# ms1616.net
KiCad netlist of a schematic drawn in EAGLE
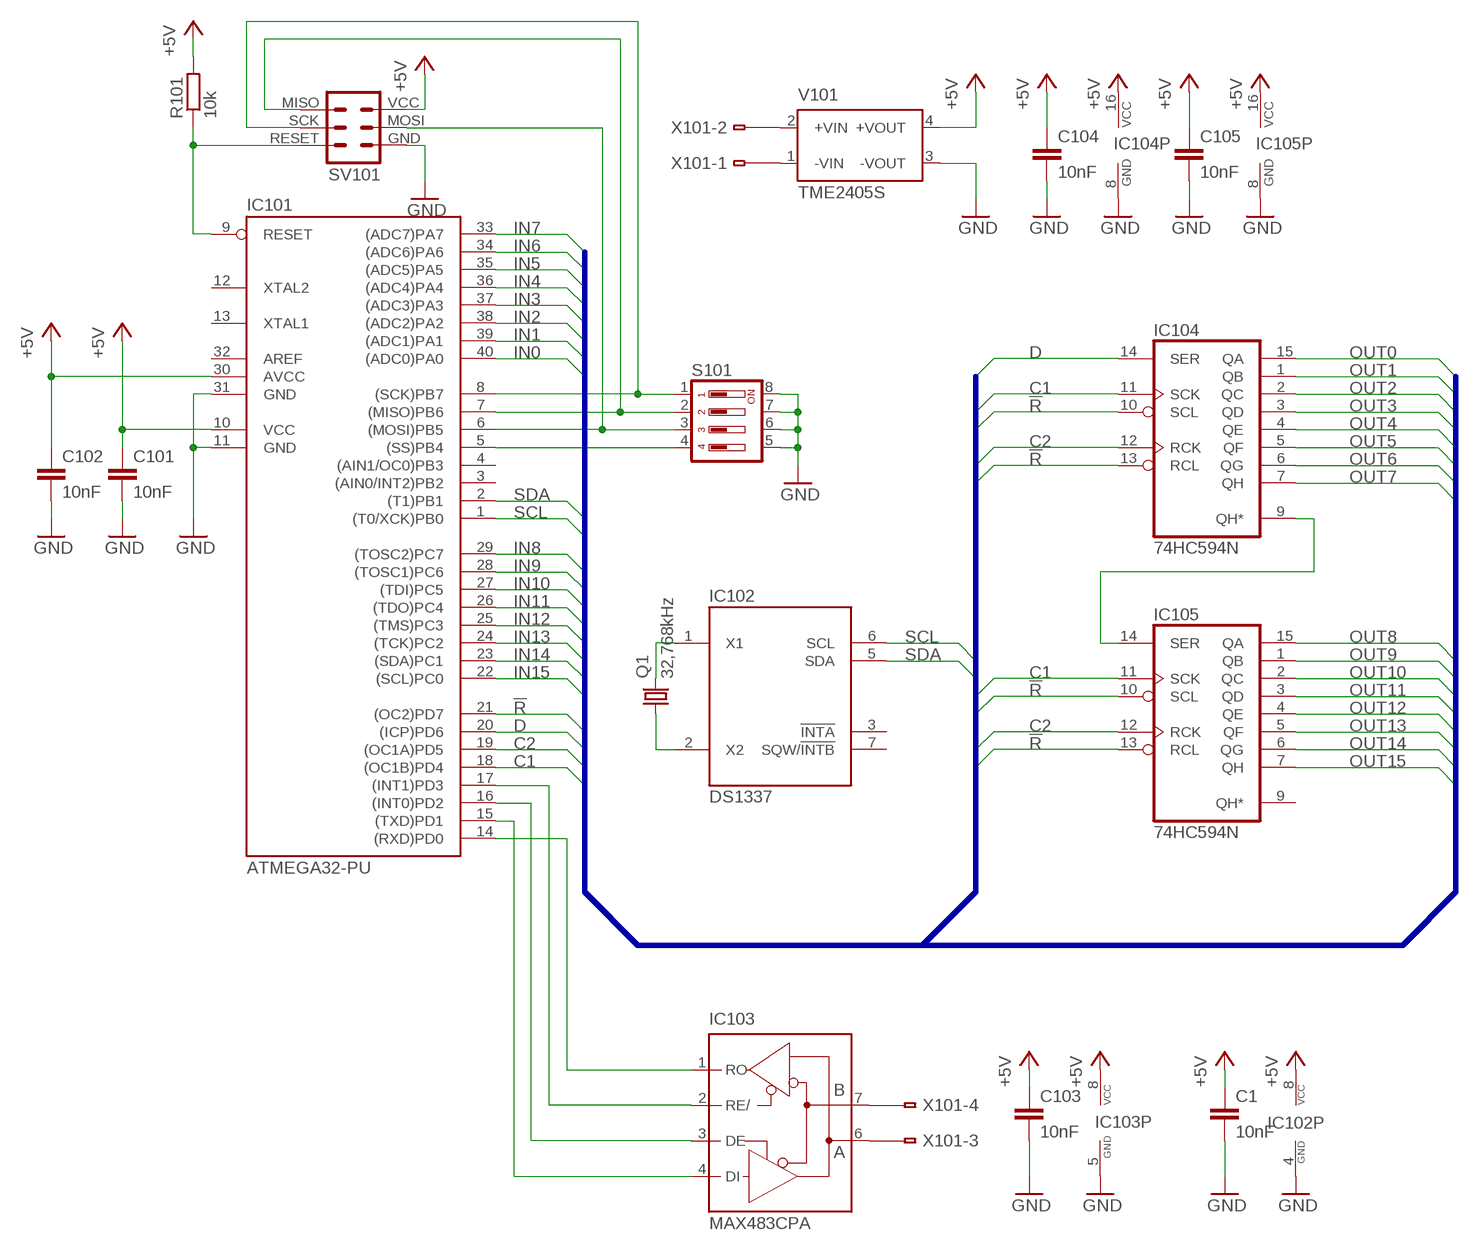
[diagram p0: schematic, sheet 1]
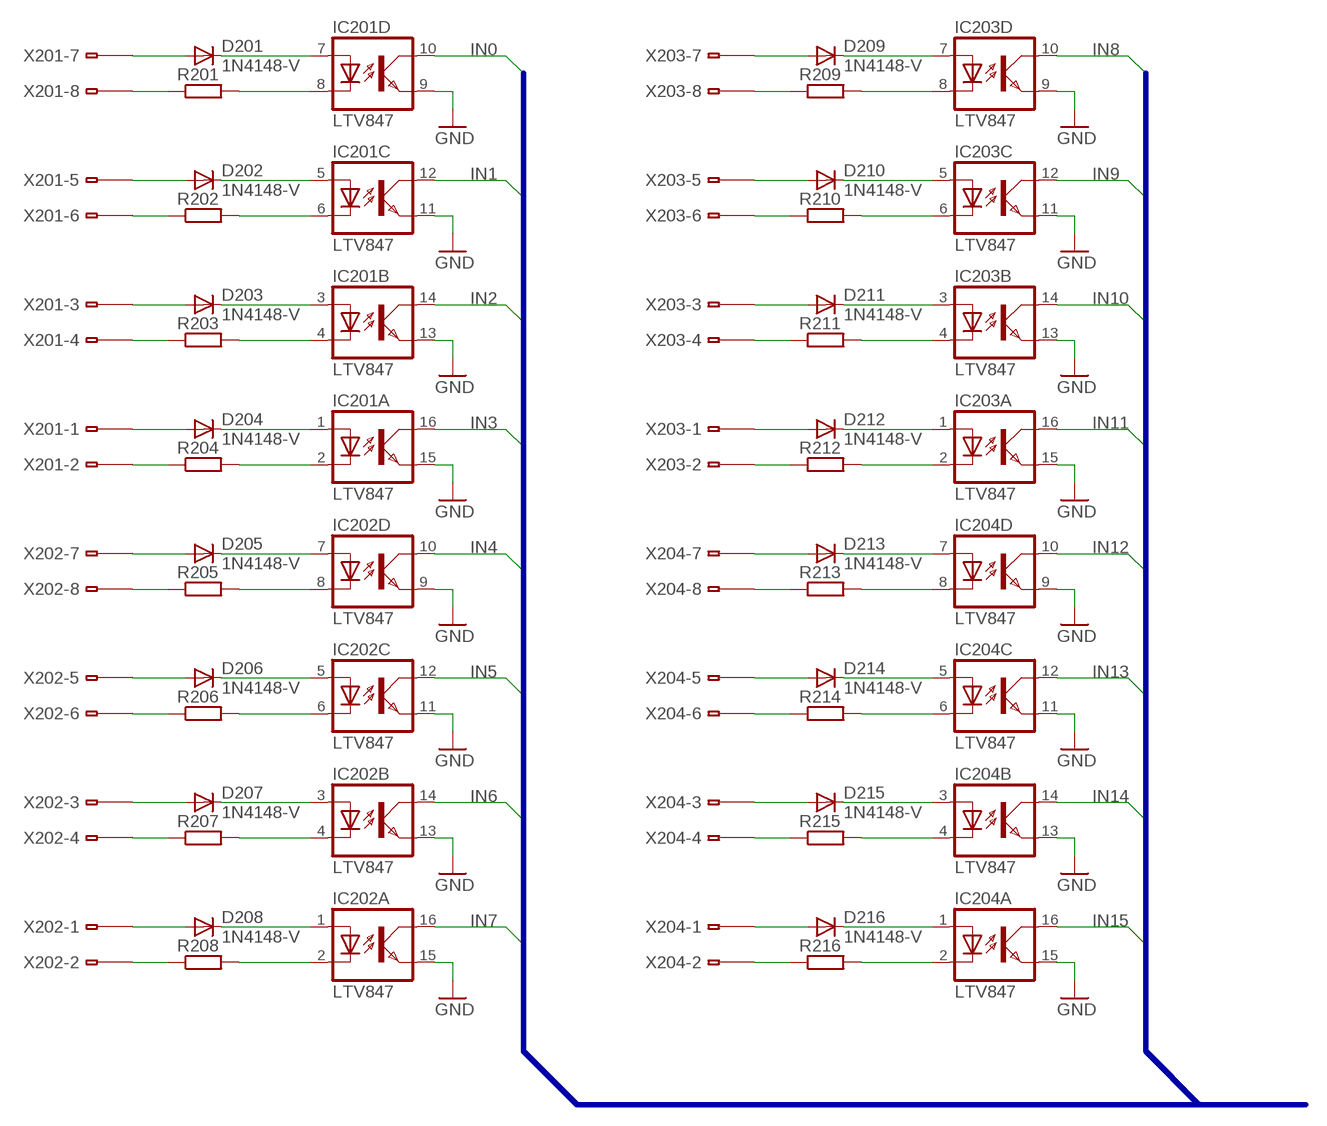
[diagram p1: schematic, sheet 2]
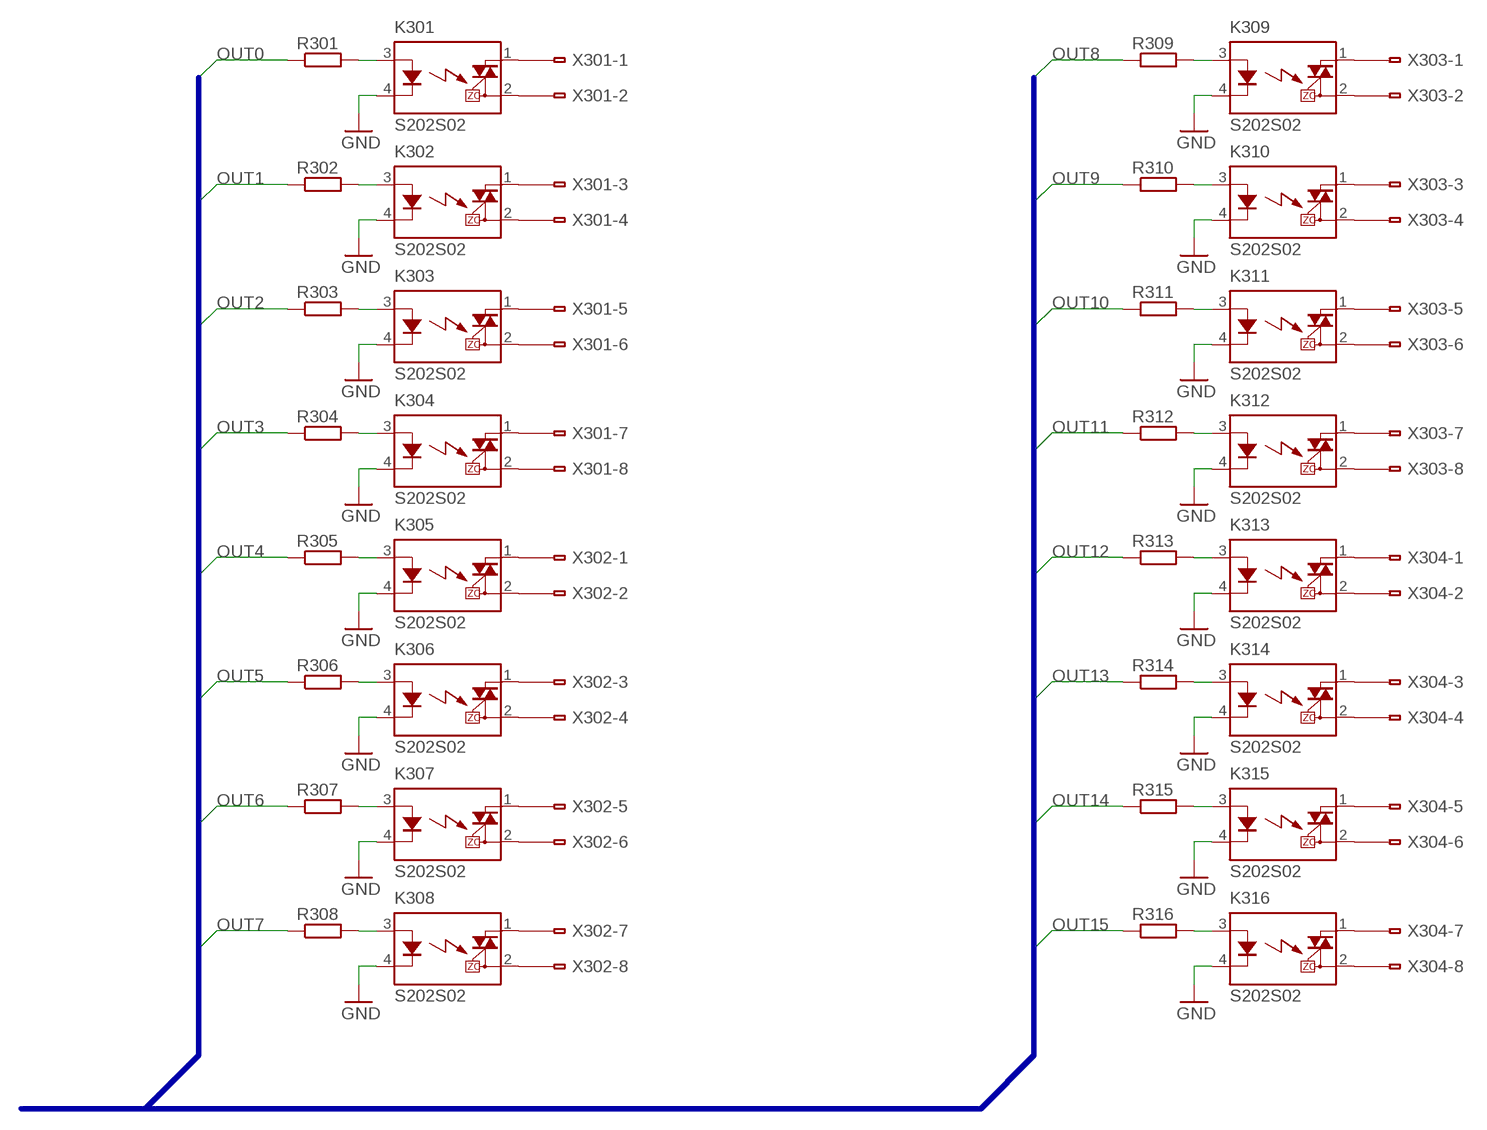
[diagram p2: schematic, sheet 3]

(export (version "E")
  (design (tool "Eeschema 10.0.6"))
  (components
    (comp (ref "K301")
      (value "S202S02")
      (footprint "eagle-import:SIP4")
      (libsource (lib "eagle-import") (part "S02S022"))
    )
    (comp (ref "K302")
      (value "S202S02")
      (footprint "eagle-import:SIP4")
      (libsource (lib "eagle-import") (part "S02S022"))
    )
    (comp (ref "K303")
      (value "S202S02")
      (footprint "eagle-import:SIP4")
      (libsource (lib "eagle-import") (part "S02S022"))
    )
    (comp (ref "K304")
      (value "S202S02")
      (footprint "eagle-import:SIP4")
      (libsource (lib "eagle-import") (part "S02S022"))
    )
    (comp (ref "K305")
      (value "S202S02")
      (footprint "eagle-import:SIP4")
      (libsource (lib "eagle-import") (part "S02S022"))
    )
    (comp (ref "K306")
      (value "S202S02")
      (footprint "eagle-import:SIP4")
      (libsource (lib "eagle-import") (part "S02S022"))
    )
    (comp (ref "K307")
      (value "S202S02")
      (footprint "eagle-import:SIP4")
      (libsource (lib "eagle-import") (part "S02S022"))
    )
    (comp (ref "K308")
      (value "S202S02")
      (footprint "eagle-import:SIP4")
      (libsource (lib "eagle-import") (part "S02S022"))
    )
    (comp (ref "K309")
      (value "S202S02")
      (footprint "eagle-import:SIP4")
      (libsource (lib "eagle-import") (part "S02S022"))
    )
    (comp (ref "K310")
      (value "S202S02")
      (footprint "eagle-import:SIP4")
      (libsource (lib "eagle-import") (part "S02S022"))
    )
    (comp (ref "K311")
      (value "S202S02")
      (footprint "eagle-import:SIP4")
      (libsource (lib "eagle-import") (part "S02S022"))
    )
    (comp (ref "K312")
      (value "S202S02")
      (footprint "eagle-import:SIP4")
      (libsource (lib "eagle-import") (part "S02S022"))
    )
    (comp (ref "K313")
      (value "S202S02")
      (footprint "eagle-import:SIP4")
      (libsource (lib "eagle-import") (part "S02S022"))
    )
    (comp (ref "K314")
      (value "S202S02")
      (footprint "eagle-import:SIP4")
      (libsource (lib "eagle-import") (part "S02S022"))
    )
    (comp (ref "K315")
      (value "S202S02")
      (footprint "eagle-import:SIP4")
      (libsource (lib "eagle-import") (part "S02S022"))
    )
    (comp (ref "K316")
      (value "S202S02")
      (footprint "eagle-import:SIP4")
      (libsource (lib "eagle-import") (part "S02S022"))
    )
    (comp (ref "R301")
      (value "R_0204/2V")
      (footprint "eagle-import:0204V")
      (libsource (lib "eagle-import") (part "R_0204/2V"))
    )
    (comp (ref "R302")
      (value "R_0204/2V")
      (footprint "eagle-import:0204V")
      (libsource (lib "eagle-import") (part "R_0204/2V"))
    )
    (comp (ref "R303")
      (value "R_0204/2V")
      (footprint "eagle-import:0204V")
      (libsource (lib "eagle-import") (part "R_0204/2V"))
    )
    (comp (ref "R304")
      (value "R_0204/2V")
      (footprint "eagle-import:0204V")
      (libsource (lib "eagle-import") (part "R_0204/2V"))
    )
    (comp (ref "R305")
      (value "R_0204/2V")
      (footprint "eagle-import:0204V")
      (libsource (lib "eagle-import") (part "R_0204/2V"))
    )
    (comp (ref "R306")
      (value "R_0204/2V")
      (footprint "eagle-import:0204V")
      (libsource (lib "eagle-import") (part "R_0204/2V"))
    )
    (comp (ref "R307")
      (value "R_0204/2V")
      (footprint "eagle-import:0204V")
      (libsource (lib "eagle-import") (part "R_0204/2V"))
    )
    (comp (ref "R308")
      (value "R_0204/2V")
      (footprint "eagle-import:0204V")
      (libsource (lib "eagle-import") (part "R_0204/2V"))
    )
    (comp (ref "R309")
      (value "R_0204/2V")
      (footprint "eagle-import:0204V")
      (libsource (lib "eagle-import") (part "R_0204/2V"))
    )
    (comp (ref "R310")
      (value "R_0204/2V")
      (footprint "eagle-import:0204V")
      (libsource (lib "eagle-import") (part "R_0204/2V"))
    )
    (comp (ref "R311")
      (value "R_0204/2V")
      (footprint "eagle-import:0204V")
      (libsource (lib "eagle-import") (part "R_0204/2V"))
    )
    (comp (ref "R312")
      (value "R_0204/2V")
      (footprint "eagle-import:0204V")
      (libsource (lib "eagle-import") (part "R_0204/2V"))
    )
    (comp (ref "R313")
      (value "R_0204/2V")
      (footprint "eagle-import:0204V")
      (libsource (lib "eagle-import") (part "R_0204/2V"))
    )
    (comp (ref "R314")
      (value "R_0204/2V")
      (footprint "eagle-import:0204V")
      (libsource (lib "eagle-import") (part "R_0204/2V"))
    )
    (comp (ref "R315")
      (value "R_0204/2V")
      (footprint "eagle-import:0204V")
      (libsource (lib "eagle-import") (part "R_0204/2V"))
    )
    (comp (ref "R316")
      (value "R_0204/2V")
      (footprint "eagle-import:0204V")
      (libsource (lib "eagle-import") (part "R_0204/2V"))
    )
    (comp (ref "X301")
      (value "233-508")
      (footprint "eagle-import:233-508")
      (libsource (lib "eagle-import") (part "233-508"))
    )
    (comp (ref "X302")
      (value "233-508")
      (footprint "eagle-import:233-508")
      (libsource (lib "eagle-import") (part "233-508"))
    )
    (comp (ref "X303")
      (value "233-508")
      (footprint "eagle-import:233-508")
      (libsource (lib "eagle-import") (part "233-508"))
    )
    (comp (ref "X304")
      (value "233-508")
      (footprint "eagle-import:233-508")
      (libsource (lib "eagle-import") (part "233-508"))
    )
    (comp (ref "C1")
      (value "10nF")
      (footprint "eagle-import:C025-025X050")
      (libsource (lib "eagle-import") (part "C_025-025X050"))
    )
    (comp (ref "C101")
      (value "10nF")
      (footprint "eagle-import:C025-025X050")
      (libsource (lib "eagle-import") (part "C_025-025X050"))
    )
    (comp (ref "C102")
      (value "10nF")
      (footprint "eagle-import:C025-025X050")
      (libsource (lib "eagle-import") (part "C_025-025X050"))
    )
    (comp (ref "C103")
      (value "10nF")
      (footprint "eagle-import:C025-025X050")
      (libsource (lib "eagle-import") (part "C_025-025X050"))
    )
    (comp (ref "C104")
      (value "10nF")
      (footprint "eagle-import:C025-025X050")
      (libsource (lib "eagle-import") (part "C_025-025X050"))
    )
    (comp (ref "C105")
      (value "10nF")
      (footprint "eagle-import:C025-025X050")
      (libsource (lib "eagle-import") (part "C_025-025X050"))
    )
    (comp (ref "IC101")
      (value "ATMEGA32-PU")
      (footprint "eagle-import:DIL40")
      (libsource (lib "eagle-import") (part "ATMEGA32-PU"))
    )
    (comp (ref "IC102")
      (value "DS1337")
      (footprint "eagle-import:DIL08")
      (libsource (lib "eagle-import") (part "DS1337"))
    )
    (comp (ref "IC103")
      (value "MAX483CPA")
      (footprint "eagle-import:DIL08")
      (libsource (lib "eagle-import") (part "MAX48CPA3"))
    )
    (comp (ref "IC104")
      (value "74HC594N")
      (footprint "eagle-import:DIL16")
      (libsource (lib "eagle-import") (part "74594NHC"))
    )
    (comp (ref "IC105")
      (value "74HC594N")
      (footprint "eagle-import:DIL16")
      (libsource (lib "eagle-import") (part "74594NHC"))
    )
    (comp (ref "Q1")
      (value "32,768kHz")
      (footprint "eagle-import:HC49_S")
      (libsource (lib "eagle-import") (part "Q_HC49S"))
    )
    (comp (ref "R101")
      (value "10k")
      (footprint "eagle-import:0204V")
      (libsource (lib "eagle-import") (part "R_0204/2V"))
    )
    (comp (ref "S101")
      (value "DIP04YL")
      (footprint "eagle-import:DIP04YL")
      (libsource (lib "eagle-import") (part "DIP04YL"))
    )
    (comp (ref "SV101")
      (value "AVR_ISP6")
      (footprint "eagle-import:ML6")
      (libsource (lib "eagle-import") (part "AVR_ISP6"))
    )
    (comp (ref "V101")
      (value "TME2405S")
      (footprint "eagle-import:TME-24V")
      (fields
        (field (name "MPN") "TME 2405S")
        (field (name "MPN_1") "TME 2405S")
        (field (name "OC_FARNELL") "1007547")
        (field (name "OC_NEWARK") "51R5329")
      )
      (libsource (lib "eagle-import") (part "TME?2405S"))
    )
    (comp (ref "X101")
      (value "233-504")
      (footprint "eagle-import:233-504")
      (libsource (lib "eagle-import") (part "233-504"))
    )
    (comp (ref "D201")
      (value "1N4148-V")
      (footprint "eagle-import:DO35-V")
      (libsource (lib "eagle-import") (part "1N4148-V"))
    )
    (comp (ref "D202")
      (value "1N4148-V")
      (footprint "eagle-import:DO35-V")
      (libsource (lib "eagle-import") (part "1N4148-V"))
    )
    (comp (ref "D203")
      (value "1N4148-V")
      (footprint "eagle-import:DO35-V")
      (libsource (lib "eagle-import") (part "1N4148-V"))
    )
    (comp (ref "D204")
      (value "1N4148-V")
      (footprint "eagle-import:DO35-V")
      (libsource (lib "eagle-import") (part "1N4148-V"))
    )
    (comp (ref "D205")
      (value "1N4148-V")
      (footprint "eagle-import:DO35-V")
      (libsource (lib "eagle-import") (part "1N4148-V"))
    )
    (comp (ref "D206")
      (value "1N4148-V")
      (footprint "eagle-import:DO35-V")
      (libsource (lib "eagle-import") (part "1N4148-V"))
    )
    (comp (ref "D207")
      (value "1N4148-V")
      (footprint "eagle-import:DO35-V")
      (libsource (lib "eagle-import") (part "1N4148-V"))
    )
    (comp (ref "D208")
      (value "1N4148-V")
      (footprint "eagle-import:DO35-V")
      (libsource (lib "eagle-import") (part "1N4148-V"))
    )
    (comp (ref "D209")
      (value "1N4148-V")
      (footprint "eagle-import:DO35-V")
      (libsource (lib "eagle-import") (part "1N4148-V"))
    )
    (comp (ref "D210")
      (value "1N4148-V")
      (footprint "eagle-import:DO35-V")
      (libsource (lib "eagle-import") (part "1N4148-V"))
    )
    (comp (ref "D211")
      (value "1N4148-V")
      (footprint "eagle-import:DO35-V")
      (libsource (lib "eagle-import") (part "1N4148-V"))
    )
    (comp (ref "D212")
      (value "1N4148-V")
      (footprint "eagle-import:DO35-V")
      (libsource (lib "eagle-import") (part "1N4148-V"))
    )
    (comp (ref "D213")
      (value "1N4148-V")
      (footprint "eagle-import:DO35-V")
      (libsource (lib "eagle-import") (part "1N4148-V"))
    )
    (comp (ref "D214")
      (value "1N4148-V")
      (footprint "eagle-import:DO35-V")
      (libsource (lib "eagle-import") (part "1N4148-V"))
    )
    (comp (ref "D215")
      (value "1N4148-V")
      (footprint "eagle-import:DO35-V")
      (libsource (lib "eagle-import") (part "1N4148-V"))
    )
    (comp (ref "D216")
      (value "1N4148-V")
      (footprint "eagle-import:DO35-V")
      (libsource (lib "eagle-import") (part "1N4148-V"))
    )
    (comp (ref "IC201")
      (value "LTV847")
      (footprint "eagle-import:DIL16")
      (libsource (lib "eagle-import") (part "LTV847"))
    )
    (comp (ref "IC202")
      (value "LTV847")
      (footprint "eagle-import:DIL16")
      (libsource (lib "eagle-import") (part "LTV847"))
    )
    (comp (ref "IC203")
      (value "LTV847")
      (footprint "eagle-import:DIL16")
      (libsource (lib "eagle-import") (part "LTV847"))
    )
    (comp (ref "IC204")
      (value "LTV847")
      (footprint "eagle-import:DIL16")
      (libsource (lib "eagle-import") (part "LTV847"))
    )
    (comp (ref "R201")
      (value "R_0204/2V")
      (footprint "eagle-import:0204V")
      (libsource (lib "eagle-import") (part "R_0204/2V"))
    )
    (comp (ref "R202")
      (value "R_0204/2V")
      (footprint "eagle-import:0204V")
      (libsource (lib "eagle-import") (part "R_0204/2V"))
    )
    (comp (ref "R203")
      (value "R_0204/2V")
      (footprint "eagle-import:0204V")
      (libsource (lib "eagle-import") (part "R_0204/2V"))
    )
    (comp (ref "R204")
      (value "R_0204/2V")
      (footprint "eagle-import:0204V")
      (libsource (lib "eagle-import") (part "R_0204/2V"))
    )
    (comp (ref "R205")
      (value "R_0204/2V")
      (footprint "eagle-import:0204V")
      (libsource (lib "eagle-import") (part "R_0204/2V"))
    )
    (comp (ref "R206")
      (value "R_0204/2V")
      (footprint "eagle-import:0204V")
      (libsource (lib "eagle-import") (part "R_0204/2V"))
    )
    (comp (ref "R207")
      (value "R_0204/2V")
      (footprint "eagle-import:0204V")
      (libsource (lib "eagle-import") (part "R_0204/2V"))
    )
    (comp (ref "R208")
      (value "R_0204/2V")
      (footprint "eagle-import:0204V")
      (libsource (lib "eagle-import") (part "R_0204/2V"))
    )
    (comp (ref "R209")
      (value "R_0204/2V")
      (footprint "eagle-import:0204V")
      (libsource (lib "eagle-import") (part "R_0204/2V"))
    )
    (comp (ref "R210")
      (value "R_0204/2V")
      (footprint "eagle-import:0204V")
      (libsource (lib "eagle-import") (part "R_0204/2V"))
    )
    (comp (ref "R211")
      (value "R_0204/2V")
      (footprint "eagle-import:0204V")
      (libsource (lib "eagle-import") (part "R_0204/2V"))
    )
    (comp (ref "R212")
      (value "R_0204/2V")
      (footprint "eagle-import:0204V")
      (libsource (lib "eagle-import") (part "R_0204/2V"))
    )
    (comp (ref "R213")
      (value "R_0204/2V")
      (footprint "eagle-import:0204V")
      (libsource (lib "eagle-import") (part "R_0204/2V"))
    )
    (comp (ref "R214")
      (value "R_0204/2V")
      (footprint "eagle-import:0204V")
      (libsource (lib "eagle-import") (part "R_0204/2V"))
    )
    (comp (ref "R215")
      (value "R_0204/2V")
      (footprint "eagle-import:0204V")
      (libsource (lib "eagle-import") (part "R_0204/2V"))
    )
    (comp (ref "R216")
      (value "R_0204/2V")
      (footprint "eagle-import:0204V")
      (libsource (lib "eagle-import") (part "R_0204/2V"))
    )
    (comp (ref "X201")
      (value "233-508")
      (footprint "eagle-import:233-508")
      (libsource (lib "eagle-import") (part "233-508"))
    )
    (comp (ref "X202")
      (value "233-508")
      (footprint "eagle-import:233-508")
      (libsource (lib "eagle-import") (part "233-508"))
    )
    (comp (ref "X203")
      (value "233-508")
      (footprint "eagle-import:233-508")
      (libsource (lib "eagle-import") (part "233-508"))
    )
    (comp (ref "X204")
      (value "233-508")
      (footprint "eagle-import:233-508")
      (libsource (lib "eagle-import") (part "233-508"))
    )
  )
  (nets
    (net (code "1") (name "+5V") (class "Default")
      (node (ref "C1") (pin "1") (pinfunction "1_1") (pintype "passive"))
      (node (ref "C101") (pin "1") (pinfunction "1_1") (pintype "passive"))
      (node (ref "C102") (pin "1") (pinfunction "1_1") (pintype "passive"))
      (node (ref "C103") (pin "1") (pinfunction "1_1") (pintype "passive"))
      (node (ref "C104") (pin "1") (pinfunction "1_1") (pintype "passive"))
      (node (ref "C105") (pin "1") (pinfunction "1_1") (pintype "passive"))
      (node (ref "IC101") (pin "10") (pinfunction "VCC_10") (pintype "power_in"))
      (node (ref "IC101") (pin "30") (pinfunction "AVCC_30") (pintype "power_in"))
      (node (ref "IC102") (pin "8") (pinfunction "VCC_8") (pintype "power_in"))
      (node (ref "IC103") (pin "8") (pinfunction "VCC_8") (pintype "power_in"))
      (node (ref "IC104") (pin "16") (pinfunction "VCC_16") (pintype "power_in"))
      (node (ref "IC105") (pin "16") (pinfunction "VCC_16") (pintype "power_in"))
      (node (ref "R101") (pin "2") (pinfunction "2_2") (pintype "passive"))
      (node (ref "SV101") (pin "VCC") (pinfunction "VCC_VCC") (pintype "passive"))
      (node (ref "V101") (pin "4") (pinfunction "+VOUT_4") (pintype "passive"))
    )
    (net (code "2") (name "C1") (class "Default")
      (node (ref "IC101") (pin "18") (pinfunction "(OC1B)PD4_18") (pintype "bidirectional"))
      (node (ref "IC104") (pin "11") (pinfunction "SCK_11") (pintype "input"))
      (node (ref "IC105") (pin "11") (pinfunction "SCK_11") (pintype "input"))
    )
    (net (code "3") (name "C2") (class "Default")
      (node (ref "IC101") (pin "19") (pinfunction "(OC1A)PD5_19") (pintype "bidirectional"))
      (node (ref "IC104") (pin "12") (pinfunction "RCK_12") (pintype "input"))
      (node (ref "IC105") (pin "12") (pinfunction "RCK_12") (pintype "input"))
    )
    (net (code "4") (name "D") (class "Default")
      (node (ref "IC101") (pin "20") (pinfunction "(ICP)PD6_20") (pintype "bidirectional"))
      (node (ref "IC104") (pin "14") (pinfunction "SER_14") (pintype "input"))
    )
    (net (code "5") (name "GND") (class "Default")
      (node (ref "C1") (pin "2") (pinfunction "2_2") (pintype "passive"))
      (node (ref "C101") (pin "2") (pinfunction "2_2") (pintype "passive"))
      (node (ref "C102") (pin "2") (pinfunction "2_2") (pintype "passive"))
      (node (ref "C103") (pin "2") (pinfunction "2_2") (pintype "passive"))
      (node (ref "C104") (pin "2") (pinfunction "2_2") (pintype "passive"))
      (node (ref "C105") (pin "2") (pinfunction "2_2") (pintype "passive"))
      (node (ref "IC101") (pin "11") (pinfunction "GND_11") (pintype "power_in"))
      (node (ref "IC101") (pin "31") (pinfunction "GND_31") (pintype "power_in"))
      (node (ref "IC102") (pin "4") (pinfunction "GND_4") (pintype "power_in"))
      (node (ref "IC103") (pin "5") (pinfunction "GND_5") (pintype "power_in"))
      (node (ref "IC104") (pin "8") (pinfunction "GND_8") (pintype "power_in"))
      (node (ref "IC105") (pin "8") (pinfunction "GND_8") (pintype "power_in"))
      (node (ref "IC201") (pin "11") (pinfunction "EMIT_11") (pintype "passive"))
      (node (ref "IC201") (pin "13") (pinfunction "EMIT_13") (pintype "passive"))
      (node (ref "IC201") (pin "15") (pinfunction "EMIT_15") (pintype "passive"))
      (node (ref "IC201") (pin "9") (pinfunction "EMIT_9") (pintype "passive"))
      (node (ref "IC202") (pin "11") (pinfunction "EMIT_11") (pintype "passive"))
      (node (ref "IC202") (pin "13") (pinfunction "EMIT_13") (pintype "passive"))
      (node (ref "IC202") (pin "15") (pinfunction "EMIT_15") (pintype "passive"))
      (node (ref "IC202") (pin "9") (pinfunction "EMIT_9") (pintype "passive"))
      (node (ref "IC203") (pin "11") (pinfunction "EMIT_11") (pintype "passive"))
      (node (ref "IC203") (pin "13") (pinfunction "EMIT_13") (pintype "passive"))
      (node (ref "IC203") (pin "15") (pinfunction "EMIT_15") (pintype "passive"))
      (node (ref "IC203") (pin "9") (pinfunction "EMIT_9") (pintype "passive"))
      (node (ref "IC204") (pin "11") (pinfunction "EMIT_11") (pintype "passive"))
      (node (ref "IC204") (pin "13") (pinfunction "EMIT_13") (pintype "passive"))
      (node (ref "IC204") (pin "15") (pinfunction "EMIT_15") (pintype "passive"))
      (node (ref "IC204") (pin "9") (pinfunction "EMIT_9") (pintype "passive"))
      (node (ref "K301") (pin "4") (pinfunction "K_4") (pintype "passive"))
      (node (ref "K302") (pin "4") (pinfunction "K_4") (pintype "passive"))
      (node (ref "K303") (pin "4") (pinfunction "K_4") (pintype "passive"))
      (node (ref "K304") (pin "4") (pinfunction "K_4") (pintype "passive"))
      (node (ref "K305") (pin "4") (pinfunction "K_4") (pintype "passive"))
      (node (ref "K306") (pin "4") (pinfunction "K_4") (pintype "passive"))
      (node (ref "K307") (pin "4") (pinfunction "K_4") (pintype "passive"))
      (node (ref "K308") (pin "4") (pinfunction "K_4") (pintype "passive"))
      (node (ref "K309") (pin "4") (pinfunction "K_4") (pintype "passive"))
      (node (ref "K310") (pin "4") (pinfunction "K_4") (pintype "passive"))
      (node (ref "K311") (pin "4") (pinfunction "K_4") (pintype "passive"))
      (node (ref "K312") (pin "4") (pinfunction "K_4") (pintype "passive"))
      (node (ref "K313") (pin "4") (pinfunction "K_4") (pintype "passive"))
      (node (ref "K314") (pin "4") (pinfunction "K_4") (pintype "passive"))
      (node (ref "K315") (pin "4") (pinfunction "K_4") (pintype "passive"))
      (node (ref "K316") (pin "4") (pinfunction "K_4") (pintype "passive"))
      (node (ref "S101") (pin "5") (pinfunction "5_5") (pintype "passive"))
      (node (ref "S101") (pin "6") (pinfunction "6_6") (pintype "passive"))
      (node (ref "S101") (pin "7") (pinfunction "7_7") (pintype "passive"))
      (node (ref "S101") (pin "8") (pinfunction "8_8") (pintype "passive"))
      (node (ref "SV101") (pin "GND") (pinfunction "GND_GND") (pintype "passive"))
      (node (ref "V101") (pin "3") (pinfunction "-VOUT_3") (pintype "passive"))
    )
    (net (code "6") (name "IN0") (class "Default")
      (node (ref "IC101") (pin "40") (pinfunction "(ADC0)PA0_40") (pintype "bidirectional"))
      (node (ref "IC201") (pin "10") (pinfunction "COL_10") (pintype "passive"))
    )
    (net (code "7") (name "IN1") (class "Default")
      (node (ref "IC101") (pin "39") (pinfunction "(ADC1)PA1_39") (pintype "bidirectional"))
      (node (ref "IC201") (pin "12") (pinfunction "COL_12") (pintype "passive"))
    )
    (net (code "8") (name "IN2") (class "Default")
      (node (ref "IC101") (pin "38") (pinfunction "(ADC2)PA2_38") (pintype "bidirectional"))
      (node (ref "IC201") (pin "14") (pinfunction "COL_14") (pintype "passive"))
    )
    (net (code "9") (name "IN3") (class "Default")
      (node (ref "IC101") (pin "37") (pinfunction "(ADC3)PA3_37") (pintype "bidirectional"))
      (node (ref "IC201") (pin "16") (pinfunction "COL_16") (pintype "passive"))
    )
    (net (code "10") (name "IN4") (class "Default")
      (node (ref "IC101") (pin "36") (pinfunction "(ADC4)PA4_36") (pintype "bidirectional"))
      (node (ref "IC202") (pin "10") (pinfunction "COL_10") (pintype "passive"))
    )
    (net (code "11") (name "IN5") (class "Default")
      (node (ref "IC101") (pin "35") (pinfunction "(ADC5)PA5_35") (pintype "bidirectional"))
      (node (ref "IC202") (pin "12") (pinfunction "COL_12") (pintype "passive"))
    )
    (net (code "12") (name "IN6") (class "Default")
      (node (ref "IC101") (pin "34") (pinfunction "(ADC6)PA6_34") (pintype "bidirectional"))
      (node (ref "IC202") (pin "14") (pinfunction "COL_14") (pintype "passive"))
    )
    (net (code "13") (name "IN7") (class "Default")
      (node (ref "IC101") (pin "33") (pinfunction "(ADC7)PA7_33") (pintype "bidirectional"))
      (node (ref "IC202") (pin "16") (pinfunction "COL_16") (pintype "passive"))
    )
    (net (code "14") (name "IN8") (class "Default")
      (node (ref "IC101") (pin "29") (pinfunction "(TOSC2)PC7_29") (pintype "bidirectional"))
      (node (ref "IC203") (pin "10") (pinfunction "COL_10") (pintype "passive"))
    )
    (net (code "15") (name "IN9") (class "Default")
      (node (ref "IC101") (pin "28") (pinfunction "(TOSC1)PC6_28") (pintype "bidirectional"))
      (node (ref "IC203") (pin "12") (pinfunction "COL_12") (pintype "passive"))
    )
    (net (code "16") (name "IN10") (class "Default")
      (node (ref "IC101") (pin "27") (pinfunction "(TDI)PC5_27") (pintype "bidirectional"))
      (node (ref "IC203") (pin "14") (pinfunction "COL_14") (pintype "passive"))
    )
    (net (code "17") (name "IN11") (class "Default")
      (node (ref "IC101") (pin "26") (pinfunction "(TDO)PC4_26") (pintype "bidirectional"))
      (node (ref "IC203") (pin "16") (pinfunction "COL_16") (pintype "passive"))
    )
    (net (code "18") (name "IN12") (class "Default")
      (node (ref "IC101") (pin "25") (pinfunction "(TMS)PC3_25") (pintype "bidirectional"))
      (node (ref "IC204") (pin "10") (pinfunction "COL_10") (pintype "passive"))
    )
    (net (code "19") (name "IN13") (class "Default")
      (node (ref "IC101") (pin "24") (pinfunction "(TCK)PC2_24") (pintype "bidirectional"))
      (node (ref "IC204") (pin "12") (pinfunction "COL_12") (pintype "passive"))
    )
    (net (code "20") (name "IN14") (class "Default")
      (node (ref "IC101") (pin "23") (pinfunction "(SDA)PC1_23") (pintype "bidirectional"))
      (node (ref "IC204") (pin "14") (pinfunction "COL_14") (pintype "passive"))
    )
    (net (code "21") (name "IN15") (class "Default")
      (node (ref "IC101") (pin "22") (pinfunction "(SCL)PC0_22") (pintype "bidirectional"))
      (node (ref "IC204") (pin "16") (pinfunction "COL_16") (pintype "passive"))
    )
    (net (code "22") (name "Net-(D201-A)") (class "Default")
      (node (ref "D201") (pin "1") (pinfunction "A_1") (pintype "passive"))
      (node (ref "X201") (pin "A7") (pinfunction "-1_A7") (pintype "passive"))
    )
    (net (code "23") (name "Net-(D201-C)") (class "Default")
      (node (ref "D201") (pin "2") (pinfunction "C_2") (pintype "passive"))
      (node (ref "IC201") (pin "7") (pinfunction "A_7") (pintype "passive"))
    )
    (net (code "24") (name "Net-(D202-A)") (class "Default")
      (node (ref "D202") (pin "1") (pinfunction "A_1") (pintype "passive"))
      (node (ref "X201") (pin "A5") (pinfunction "-1_A5") (pintype "passive"))
    )
    (net (code "25") (name "Net-(D202-C)") (class "Default")
      (node (ref "D202") (pin "2") (pinfunction "C_2") (pintype "passive"))
      (node (ref "IC201") (pin "5") (pinfunction "A_5") (pintype "passive"))
    )
    (net (code "26") (name "Net-(D203-A)") (class "Default")
      (node (ref "D203") (pin "1") (pinfunction "A_1") (pintype "passive"))
      (node (ref "X201") (pin "A3") (pinfunction "-1_A3") (pintype "passive"))
    )
    (net (code "27") (name "Net-(D203-C)") (class "Default")
      (node (ref "D203") (pin "2") (pinfunction "C_2") (pintype "passive"))
      (node (ref "IC201") (pin "3") (pinfunction "A_3") (pintype "passive"))
    )
    (net (code "28") (name "Net-(D204-A)") (class "Default")
      (node (ref "D204") (pin "1") (pinfunction "A_1") (pintype "passive"))
      (node (ref "X201") (pin "A1") (pinfunction "-1_A1") (pintype "passive"))
    )
    (net (code "29") (name "Net-(D204-C)") (class "Default")
      (node (ref "D204") (pin "2") (pinfunction "C_2") (pintype "passive"))
      (node (ref "IC201") (pin "1") (pinfunction "A_1") (pintype "passive"))
    )
    (net (code "30") (name "Net-(D205-A)") (class "Default")
      (node (ref "D205") (pin "1") (pinfunction "A_1") (pintype "passive"))
      (node (ref "X202") (pin "A7") (pinfunction "-1_A7") (pintype "passive"))
    )
    (net (code "31") (name "Net-(D205-C)") (class "Default")
      (node (ref "D205") (pin "2") (pinfunction "C_2") (pintype "passive"))
      (node (ref "IC202") (pin "7") (pinfunction "A_7") (pintype "passive"))
    )
    (net (code "32") (name "Net-(D206-A)") (class "Default")
      (node (ref "D206") (pin "1") (pinfunction "A_1") (pintype "passive"))
      (node (ref "X202") (pin "A5") (pinfunction "-1_A5") (pintype "passive"))
    )
    (net (code "33") (name "Net-(D206-C)") (class "Default")
      (node (ref "D206") (pin "2") (pinfunction "C_2") (pintype "passive"))
      (node (ref "IC202") (pin "5") (pinfunction "A_5") (pintype "passive"))
    )
    (net (code "34") (name "Net-(D207-A)") (class "Default")
      (node (ref "D207") (pin "1") (pinfunction "A_1") (pintype "passive"))
      (node (ref "X202") (pin "A3") (pinfunction "-1_A3") (pintype "passive"))
    )
    (net (code "35") (name "Net-(D207-C)") (class "Default")
      (node (ref "D207") (pin "2") (pinfunction "C_2") (pintype "passive"))
      (node (ref "IC202") (pin "3") (pinfunction "A_3") (pintype "passive"))
    )
    (net (code "36") (name "Net-(D208-A)") (class "Default")
      (node (ref "D208") (pin "1") (pinfunction "A_1") (pintype "passive"))
      (node (ref "X202") (pin "A1") (pinfunction "-1_A1") (pintype "passive"))
    )
    (net (code "37") (name "Net-(D208-C)") (class "Default")
      (node (ref "D208") (pin "2") (pinfunction "C_2") (pintype "passive"))
      (node (ref "IC202") (pin "1") (pinfunction "A_1") (pintype "passive"))
    )
    (net (code "38") (name "Net-(D209-A)") (class "Default")
      (node (ref "D209") (pin "1") (pinfunction "A_1") (pintype "passive"))
      (node (ref "X203") (pin "A7") (pinfunction "-1_A7") (pintype "passive"))
    )
    (net (code "39") (name "Net-(D209-C)") (class "Default")
      (node (ref "D209") (pin "2") (pinfunction "C_2") (pintype "passive"))
      (node (ref "IC203") (pin "7") (pinfunction "A_7") (pintype "passive"))
    )
    (net (code "40") (name "Net-(D210-A)") (class "Default")
      (node (ref "D210") (pin "1") (pinfunction "A_1") (pintype "passive"))
      (node (ref "X203") (pin "A5") (pinfunction "-1_A5") (pintype "passive"))
    )
    (net (code "41") (name "Net-(D210-C)") (class "Default")
      (node (ref "D210") (pin "2") (pinfunction "C_2") (pintype "passive"))
      (node (ref "IC203") (pin "5") (pinfunction "A_5") (pintype "passive"))
    )
    (net (code "42") (name "Net-(D211-A)") (class "Default")
      (node (ref "D211") (pin "1") (pinfunction "A_1") (pintype "passive"))
      (node (ref "X203") (pin "A3") (pinfunction "-1_A3") (pintype "passive"))
    )
    (net (code "43") (name "Net-(D211-C)") (class "Default")
      (node (ref "D211") (pin "2") (pinfunction "C_2") (pintype "passive"))
      (node (ref "IC203") (pin "3") (pinfunction "A_3") (pintype "passive"))
    )
    (net (code "44") (name "Net-(D212-A)") (class "Default")
      (node (ref "D212") (pin "1") (pinfunction "A_1") (pintype "passive"))
      (node (ref "X203") (pin "A1") (pinfunction "-1_A1") (pintype "passive"))
    )
    (net (code "45") (name "Net-(D212-C)") (class "Default")
      (node (ref "D212") (pin "2") (pinfunction "C_2") (pintype "passive"))
      (node (ref "IC203") (pin "1") (pinfunction "A_1") (pintype "passive"))
    )
    (net (code "46") (name "Net-(D213-A)") (class "Default")
      (node (ref "D213") (pin "1") (pinfunction "A_1") (pintype "passive"))
      (node (ref "X204") (pin "A7") (pinfunction "-1_A7") (pintype "passive"))
    )
    (net (code "47") (name "Net-(D213-C)") (class "Default")
      (node (ref "D213") (pin "2") (pinfunction "C_2") (pintype "passive"))
      (node (ref "IC204") (pin "7") (pinfunction "A_7") (pintype "passive"))
    )
    (net (code "48") (name "Net-(D214-A)") (class "Default")
      (node (ref "D214") (pin "1") (pinfunction "A_1") (pintype "passive"))
      (node (ref "X204") (pin "A5") (pinfunction "-1_A5") (pintype "passive"))
    )
    (net (code "49") (name "Net-(D214-C)") (class "Default")
      (node (ref "D214") (pin "2") (pinfunction "C_2") (pintype "passive"))
      (node (ref "IC204") (pin "5") (pinfunction "A_5") (pintype "passive"))
    )
    (net (code "50") (name "Net-(D215-A)") (class "Default")
      (node (ref "D215") (pin "1") (pinfunction "A_1") (pintype "passive"))
      (node (ref "X204") (pin "A3") (pinfunction "-1_A3") (pintype "passive"))
    )
    (net (code "51") (name "Net-(D215-C)") (class "Default")
      (node (ref "D215") (pin "2") (pinfunction "C_2") (pintype "passive"))
      (node (ref "IC204") (pin "3") (pinfunction "A_3") (pintype "passive"))
    )
    (net (code "52") (name "Net-(D216-A)") (class "Default")
      (node (ref "D216") (pin "1") (pinfunction "A_1") (pintype "passive"))
      (node (ref "X204") (pin "A1") (pinfunction "-1_A1") (pintype "passive"))
    )
    (net (code "53") (name "Net-(D216-C)") (class "Default")
      (node (ref "D216") (pin "2") (pinfunction "C_2") (pintype "passive"))
      (node (ref "IC204") (pin "1") (pinfunction "A_1") (pintype "passive"))
    )
    (net (code "54") (name "Net-(IC101-(INT0)PD2)") (class "Default")
      (node (ref "IC101") (pin "16") (pinfunction "(INT0)PD2_16") (pintype "bidirectional"))
      (node (ref "IC103") (pin "3") (pinfunction "DE_3") (pintype "input"))
    )
    (net (code "55") (name "Net-(IC101-(INT1)PD3)") (class "Default")
      (node (ref "IC101") (pin "17") (pinfunction "(INT1)PD3_17") (pintype "bidirectional"))
      (node (ref "IC103") (pin "2") (pinfunction "RE/_2") (pintype "input"))
    )
    (net (code "56") (name "Net-(IC101-(MISO)PB6)") (class "Default")
      (node (ref "IC101") (pin "7") (pinfunction "(MISO)PB6_7") (pintype "bidirectional"))
      (node (ref "S101") (pin "2") (pinfunction "2_2") (pintype "passive"))
      (node (ref "SV101") (pin "MISO") (pinfunction "MISO_MISO") (pintype "passive"))
    )
    (net (code "57") (name "Net-(IC101-(MOSI)PB5)") (class "Default")
      (node (ref "IC101") (pin "6") (pinfunction "(MOSI)PB5_6") (pintype "bidirectional"))
      (node (ref "S101") (pin "3") (pinfunction "3_3") (pintype "passive"))
      (node (ref "SV101") (pin "MOSI") (pinfunction "MOSI_MOSI") (pintype "passive"))
    )
    (net (code "58") (name "Net-(IC101-(RXD)PD0)") (class "Default")
      (node (ref "IC101") (pin "14") (pinfunction "(RXD)PD0_14") (pintype "bidirectional"))
      (node (ref "IC103") (pin "1") (pinfunction "RO_1") (pintype "output"))
    )
    (net (code "59") (name "Net-(IC101-(SCK)PB7)") (class "Default")
      (node (ref "IC101") (pin "8") (pinfunction "(SCK)PB7_8") (pintype "bidirectional"))
      (node (ref "S101") (pin "1") (pinfunction "1_1") (pintype "passive"))
      (node (ref "SV101") (pin "SCK") (pinfunction "SCK_SCK") (pintype "passive"))
    )
    (net (code "60") (name "Net-(IC101-(SS)PB4)") (class "Default")
      (node (ref "IC101") (pin "5") (pinfunction "(SS)PB4_5") (pintype "bidirectional"))
      (node (ref "S101") (pin "4") (pinfunction "4_4") (pintype "passive"))
    )
    (net (code "61") (name "Net-(IC101-(TXD)PD1)") (class "Default")
      (node (ref "IC101") (pin "15") (pinfunction "(TXD)PD1_15") (pintype "bidirectional"))
      (node (ref "IC103") (pin "4") (pinfunction "DI_4") (pintype "input"))
    )
    (net (code "62") (name "Net-(IC101-RESET)") (class "Default")
      (node (ref "IC101") (pin "9") (pinfunction "RESET_9") (pintype "input"))
      (node (ref "R101") (pin "1") (pinfunction "1_1") (pintype "passive"))
      (node (ref "SV101") (pin "RESET") (pinfunction "RESET_RESET") (pintype "passive"))
    )
    (net (code "63") (name "Net-(IC102A-X1)") (class "Default")
      (node (ref "IC102") (pin "1") (pinfunction "X1_1") (pintype "bidirectional"))
      (node (ref "Q1") (pin "2") (pinfunction "2_2") (pintype "passive"))
    )
    (net (code "64") (name "Net-(IC102A-X2)") (class "Default")
      (node (ref "IC102") (pin "2") (pinfunction "X2_2") (pintype "bidirectional"))
      (node (ref "Q1") (pin "1") (pinfunction "1_1") (pintype "passive"))
    )
    (net (code "65") (name "Net-(IC103A-A)") (class "Default")
      (node (ref "IC103") (pin "6") (pinfunction "A_6") (pintype "passive"))
      (node (ref "X101") (pin "A3") (pinfunction "-1_A3") (pintype "passive"))
    )
    (net (code "66") (name "Net-(IC103A-B)") (class "Default")
      (node (ref "IC103") (pin "7") (pinfunction "B_7") (pintype "passive"))
      (node (ref "X101") (pin "A4") (pinfunction "-1_A4") (pintype "passive"))
    )
    (net (code "67") (name "Net-(IC104A-QH*)") (class "Default")
      (node (ref "IC104") (pin "9") (pinfunction "QH*_9") (pintype "output"))
      (node (ref "IC105") (pin "14") (pinfunction "SER_14") (pintype "input"))
    )
    (net (code "68") (name "Net-(IC201A-C)") (class "Default")
      (node (ref "IC201") (pin "2") (pinfunction "C_2") (pintype "passive"))
      (node (ref "R204") (pin "2") (pinfunction "2_2") (pintype "passive"))
    )
    (net (code "69") (name "Net-(IC201B-C)") (class "Default")
      (node (ref "IC201") (pin "4") (pinfunction "C_4") (pintype "passive"))
      (node (ref "R203") (pin "2") (pinfunction "2_2") (pintype "passive"))
    )
    (net (code "70") (name "Net-(IC201C-C)") (class "Default")
      (node (ref "IC201") (pin "6") (pinfunction "C_6") (pintype "passive"))
      (node (ref "R202") (pin "2") (pinfunction "2_2") (pintype "passive"))
    )
    (net (code "71") (name "Net-(IC201D-C)") (class "Default")
      (node (ref "IC201") (pin "8") (pinfunction "C_8") (pintype "passive"))
      (node (ref "R201") (pin "2") (pinfunction "2_2") (pintype "passive"))
    )
    (net (code "72") (name "Net-(IC202A-C)") (class "Default")
      (node (ref "IC202") (pin "2") (pinfunction "C_2") (pintype "passive"))
      (node (ref "R208") (pin "2") (pinfunction "2_2") (pintype "passive"))
    )
    (net (code "73") (name "Net-(IC202B-C)") (class "Default")
      (node (ref "IC202") (pin "4") (pinfunction "C_4") (pintype "passive"))
      (node (ref "R207") (pin "2") (pinfunction "2_2") (pintype "passive"))
    )
    (net (code "74") (name "Net-(IC202C-C)") (class "Default")
      (node (ref "IC202") (pin "6") (pinfunction "C_6") (pintype "passive"))
      (node (ref "R206") (pin "2") (pinfunction "2_2") (pintype "passive"))
    )
    (net (code "75") (name "Net-(IC202D-C)") (class "Default")
      (node (ref "IC202") (pin "8") (pinfunction "C_8") (pintype "passive"))
      (node (ref "R205") (pin "2") (pinfunction "2_2") (pintype "passive"))
    )
    (net (code "76") (name "Net-(IC203A-C)") (class "Default")
      (node (ref "IC203") (pin "2") (pinfunction "C_2") (pintype "passive"))
      (node (ref "R212") (pin "2") (pinfunction "2_2") (pintype "passive"))
    )
    (net (code "77") (name "Net-(IC203B-C)") (class "Default")
      (node (ref "IC203") (pin "4") (pinfunction "C_4") (pintype "passive"))
      (node (ref "R211") (pin "2") (pinfunction "2_2") (pintype "passive"))
    )
    (net (code "78") (name "Net-(IC203C-C)") (class "Default")
      (node (ref "IC203") (pin "6") (pinfunction "C_6") (pintype "passive"))
      (node (ref "R210") (pin "2") (pinfunction "2_2") (pintype "passive"))
    )
    (net (code "79") (name "Net-(IC203D-C)") (class "Default")
      (node (ref "IC203") (pin "8") (pinfunction "C_8") (pintype "passive"))
      (node (ref "R209") (pin "2") (pinfunction "2_2") (pintype "passive"))
    )
    (net (code "80") (name "Net-(IC204A-C)") (class "Default")
      (node (ref "IC204") (pin "2") (pinfunction "C_2") (pintype "passive"))
      (node (ref "R216") (pin "2") (pinfunction "2_2") (pintype "passive"))
    )
    (net (code "81") (name "Net-(IC204B-C)") (class "Default")
      (node (ref "IC204") (pin "4") (pinfunction "C_4") (pintype "passive"))
      (node (ref "R215") (pin "2") (pinfunction "2_2") (pintype "passive"))
    )
    (net (code "82") (name "Net-(IC204C-C)") (class "Default")
      (node (ref "IC204") (pin "6") (pinfunction "C_6") (pintype "passive"))
      (node (ref "R214") (pin "2") (pinfunction "2_2") (pintype "passive"))
    )
    (net (code "83") (name "Net-(IC204D-C)") (class "Default")
      (node (ref "IC204") (pin "8") (pinfunction "C_8") (pintype "passive"))
      (node (ref "R213") (pin "2") (pinfunction "2_2") (pintype "passive"))
    )
    (net (code "84") (name "Net-(K301-A)") (class "Default")
      (node (ref "K301") (pin "3") (pinfunction "A_3") (pintype "passive"))
      (node (ref "R301") (pin "2") (pinfunction "2_2") (pintype "passive"))
    )
    (net (code "85") (name "Net-(K301-DS1)") (class "Default")
      (node (ref "K301") (pin "1") (pinfunction "DS1_1") (pintype "passive"))
      (node (ref "X301") (pin "A1") (pinfunction "-1_A1") (pintype "passive"))
    )
    (net (code "86") (name "Net-(K301-DS2)") (class "Default")
      (node (ref "K301") (pin "2") (pinfunction "DS2_2") (pintype "passive"))
      (node (ref "X301") (pin "A2") (pinfunction "-1_A2") (pintype "passive"))
    )
    (net (code "87") (name "Net-(K302-A)") (class "Default")
      (node (ref "K302") (pin "3") (pinfunction "A_3") (pintype "passive"))
      (node (ref "R302") (pin "2") (pinfunction "2_2") (pintype "passive"))
    )
    (net (code "88") (name "Net-(K302-DS1)") (class "Default")
      (node (ref "K302") (pin "1") (pinfunction "DS1_1") (pintype "passive"))
      (node (ref "X301") (pin "A3") (pinfunction "-1_A3") (pintype "passive"))
    )
    (net (code "89") (name "Net-(K302-DS2)") (class "Default")
      (node (ref "K302") (pin "2") (pinfunction "DS2_2") (pintype "passive"))
      (node (ref "X301") (pin "A4") (pinfunction "-1_A4") (pintype "passive"))
    )
    (net (code "90") (name "Net-(K303-A)") (class "Default")
      (node (ref "K303") (pin "3") (pinfunction "A_3") (pintype "passive"))
      (node (ref "R303") (pin "2") (pinfunction "2_2") (pintype "passive"))
    )
    (net (code "91") (name "Net-(K303-DS1)") (class "Default")
      (node (ref "K303") (pin "1") (pinfunction "DS1_1") (pintype "passive"))
      (node (ref "X301") (pin "A5") (pinfunction "-1_A5") (pintype "passive"))
    )
    (net (code "92") (name "Net-(K303-DS2)") (class "Default")
      (node (ref "K303") (pin "2") (pinfunction "DS2_2") (pintype "passive"))
      (node (ref "X301") (pin "A6") (pinfunction "-1_A6") (pintype "passive"))
    )
    (net (code "93") (name "Net-(K304-A)") (class "Default")
      (node (ref "K304") (pin "3") (pinfunction "A_3") (pintype "passive"))
      (node (ref "R304") (pin "2") (pinfunction "2_2") (pintype "passive"))
    )
    (net (code "94") (name "Net-(K304-DS1)") (class "Default")
      (node (ref "K304") (pin "1") (pinfunction "DS1_1") (pintype "passive"))
      (node (ref "X301") (pin "A7") (pinfunction "-1_A7") (pintype "passive"))
    )
    (net (code "95") (name "Net-(K304-DS2)") (class "Default")
      (node (ref "K304") (pin "2") (pinfunction "DS2_2") (pintype "passive"))
      (node (ref "X301") (pin "A8") (pinfunction "-1_A8") (pintype "passive"))
    )
    (net (code "96") (name "Net-(K305-A)") (class "Default")
      (node (ref "K305") (pin "3") (pinfunction "A_3") (pintype "passive"))
      (node (ref "R305") (pin "2") (pinfunction "2_2") (pintype "passive"))
    )
    (net (code "97") (name "Net-(K305-DS1)") (class "Default")
      (node (ref "K305") (pin "1") (pinfunction "DS1_1") (pintype "passive"))
      (node (ref "X302") (pin "A1") (pinfunction "-1_A1") (pintype "passive"))
    )
    (net (code "98") (name "Net-(K305-DS2)") (class "Default")
      (node (ref "K305") (pin "2") (pinfunction "DS2_2") (pintype "passive"))
      (node (ref "X302") (pin "A2") (pinfunction "-1_A2") (pintype "passive"))
    )
    (net (code "99") (name "Net-(K306-A)") (class "Default")
      (node (ref "K306") (pin "3") (pinfunction "A_3") (pintype "passive"))
      (node (ref "R306") (pin "2") (pinfunction "2_2") (pintype "passive"))
    )
    (net (code "100") (name "Net-(K306-DS1)") (class "Default")
      (node (ref "K306") (pin "1") (pinfunction "DS1_1") (pintype "passive"))
      (node (ref "X302") (pin "A3") (pinfunction "-1_A3") (pintype "passive"))
    )
    (net (code "101") (name "Net-(K306-DS2)") (class "Default")
      (node (ref "K306") (pin "2") (pinfunction "DS2_2") (pintype "passive"))
      (node (ref "X302") (pin "A4") (pinfunction "-1_A4") (pintype "passive"))
    )
    (net (code "102") (name "Net-(K307-A)") (class "Default")
      (node (ref "K307") (pin "3") (pinfunction "A_3") (pintype "passive"))
      (node (ref "R307") (pin "2") (pinfunction "2_2") (pintype "passive"))
    )
    (net (code "103") (name "Net-(K307-DS1)") (class "Default")
      (node (ref "K307") (pin "1") (pinfunction "DS1_1") (pintype "passive"))
      (node (ref "X302") (pin "A5") (pinfunction "-1_A5") (pintype "passive"))
    )
    (net (code "104") (name "Net-(K307-DS2)") (class "Default")
      (node (ref "K307") (pin "2") (pinfunction "DS2_2") (pintype "passive"))
      (node (ref "X302") (pin "A6") (pinfunction "-1_A6") (pintype "passive"))
    )
    (net (code "105") (name "Net-(K308-A)") (class "Default")
      (node (ref "K308") (pin "3") (pinfunction "A_3") (pintype "passive"))
      (node (ref "R308") (pin "2") (pinfunction "2_2") (pintype "passive"))
    )
    (net (code "106") (name "Net-(K308-DS1)") (class "Default")
      (node (ref "K308") (pin "1") (pinfunction "DS1_1") (pintype "passive"))
      (node (ref "X302") (pin "A7") (pinfunction "-1_A7") (pintype "passive"))
    )
    (net (code "107") (name "Net-(K308-DS2)") (class "Default")
      (node (ref "K308") (pin "2") (pinfunction "DS2_2") (pintype "passive"))
      (node (ref "X302") (pin "A8") (pinfunction "-1_A8") (pintype "passive"))
    )
    (net (code "108") (name "Net-(K309-A)") (class "Default")
      (node (ref "K309") (pin "3") (pinfunction "A_3") (pintype "passive"))
      (node (ref "R309") (pin "2") (pinfunction "2_2") (pintype "passive"))
    )
    (net (code "109") (name "Net-(K309-DS1)") (class "Default")
      (node (ref "K309") (pin "1") (pinfunction "DS1_1") (pintype "passive"))
      (node (ref "X303") (pin "A1") (pinfunction "-1_A1") (pintype "passive"))
    )
    (net (code "110") (name "Net-(K309-DS2)") (class "Default")
      (node (ref "K309") (pin "2") (pinfunction "DS2_2") (pintype "passive"))
      (node (ref "X303") (pin "A2") (pinfunction "-1_A2") (pintype "passive"))
    )
    (net (code "111") (name "Net-(K310-A)") (class "Default")
      (node (ref "K310") (pin "3") (pinfunction "A_3") (pintype "passive"))
      (node (ref "R310") (pin "2") (pinfunction "2_2") (pintype "passive"))
    )
    (net (code "112") (name "Net-(K310-DS1)") (class "Default")
      (node (ref "K310") (pin "1") (pinfunction "DS1_1") (pintype "passive"))
      (node (ref "X303") (pin "A3") (pinfunction "-1_A3") (pintype "passive"))
    )
    (net (code "113") (name "Net-(K310-DS2)") (class "Default")
      (node (ref "K310") (pin "2") (pinfunction "DS2_2") (pintype "passive"))
      (node (ref "X303") (pin "A4") (pinfunction "-1_A4") (pintype "passive"))
    )
    (net (code "114") (name "Net-(K311-A)") (class "Default")
      (node (ref "K311") (pin "3") (pinfunction "A_3") (pintype "passive"))
      (node (ref "R311") (pin "2") (pinfunction "2_2") (pintype "passive"))
    )
    (net (code "115") (name "Net-(K311-DS1)") (class "Default")
      (node (ref "K311") (pin "1") (pinfunction "DS1_1") (pintype "passive"))
      (node (ref "X303") (pin "A5") (pinfunction "-1_A5") (pintype "passive"))
    )
    (net (code "116") (name "Net-(K311-DS2)") (class "Default")
      (node (ref "K311") (pin "2") (pinfunction "DS2_2") (pintype "passive"))
      (node (ref "X303") (pin "A6") (pinfunction "-1_A6") (pintype "passive"))
    )
    (net (code "117") (name "Net-(K312-A)") (class "Default")
      (node (ref "K312") (pin "3") (pinfunction "A_3") (pintype "passive"))
      (node (ref "R312") (pin "2") (pinfunction "2_2") (pintype "passive"))
    )
    (net (code "118") (name "Net-(K312-DS1)") (class "Default")
      (node (ref "K312") (pin "1") (pinfunction "DS1_1") (pintype "passive"))
      (node (ref "X303") (pin "A7") (pinfunction "-1_A7") (pintype "passive"))
    )
    (net (code "119") (name "Net-(K312-DS2)") (class "Default")
      (node (ref "K312") (pin "2") (pinfunction "DS2_2") (pintype "passive"))
      (node (ref "X303") (pin "A8") (pinfunction "-1_A8") (pintype "passive"))
    )
    (net (code "120") (name "Net-(K313-A)") (class "Default")
      (node (ref "K313") (pin "3") (pinfunction "A_3") (pintype "passive"))
      (node (ref "R313") (pin "2") (pinfunction "2_2") (pintype "passive"))
    )
    (net (code "121") (name "Net-(K313-DS1)") (class "Default")
      (node (ref "K313") (pin "1") (pinfunction "DS1_1") (pintype "passive"))
      (node (ref "X304") (pin "A1") (pinfunction "-1_A1") (pintype "passive"))
    )
    (net (code "122") (name "Net-(K313-DS2)") (class "Default")
      (node (ref "K313") (pin "2") (pinfunction "DS2_2") (pintype "passive"))
      (node (ref "X304") (pin "A2") (pinfunction "-1_A2") (pintype "passive"))
    )
    (net (code "123") (name "Net-(K314-A)") (class "Default")
      (node (ref "K314") (pin "3") (pinfunction "A_3") (pintype "passive"))
      (node (ref "R314") (pin "2") (pinfunction "2_2") (pintype "passive"))
    )
    (net (code "124") (name "Net-(K314-DS1)") (class "Default")
      (node (ref "K314") (pin "1") (pinfunction "DS1_1") (pintype "passive"))
      (node (ref "X304") (pin "A3") (pinfunction "-1_A3") (pintype "passive"))
    )
    (net (code "125") (name "Net-(K314-DS2)") (class "Default")
      (node (ref "K314") (pin "2") (pinfunction "DS2_2") (pintype "passive"))
      (node (ref "X304") (pin "A4") (pinfunction "-1_A4") (pintype "passive"))
    )
    (net (code "126") (name "Net-(K315-A)") (class "Default")
      (node (ref "K315") (pin "3") (pinfunction "A_3") (pintype "passive"))
      (node (ref "R315") (pin "2") (pinfunction "2_2") (pintype "passive"))
    )
    (net (code "127") (name "Net-(K315-DS1)") (class "Default")
      (node (ref "K315") (pin "1") (pinfunction "DS1_1") (pintype "passive"))
      (node (ref "X304") (pin "A5") (pinfunction "-1_A5") (pintype "passive"))
    )
    (net (code "128") (name "Net-(K315-DS2)") (class "Default")
      (node (ref "K315") (pin "2") (pinfunction "DS2_2") (pintype "passive"))
      (node (ref "X304") (pin "A6") (pinfunction "-1_A6") (pintype "passive"))
    )
    (net (code "129") (name "Net-(K316-A)") (class "Default")
      (node (ref "K316") (pin "3") (pinfunction "A_3") (pintype "passive"))
      (node (ref "R316") (pin "2") (pinfunction "2_2") (pintype "passive"))
    )
    (net (code "130") (name "Net-(K316-DS1)") (class "Default")
      (node (ref "K316") (pin "1") (pinfunction "DS1_1") (pintype "passive"))
      (node (ref "X304") (pin "A7") (pinfunction "-1_A7") (pintype "passive"))
    )
    (net (code "131") (name "Net-(K316-DS2)") (class "Default")
      (node (ref "K316") (pin "2") (pinfunction "DS2_2") (pintype "passive"))
      (node (ref "X304") (pin "A8") (pinfunction "-1_A8") (pintype "passive"))
    )
    (net (code "132") (name "Net-(V101-+VIN)") (class "Default")
      (node (ref "V101") (pin "2") (pinfunction "+VIN_2") (pintype "passive"))
      (node (ref "X101") (pin "A2") (pinfunction "-1_A2") (pintype "passive"))
    )
    (net (code "133") (name "Net-(V101--VIN)") (class "Default")
      (node (ref "V101") (pin "1") (pinfunction "-VIN_1") (pintype "passive"))
      (node (ref "X101") (pin "A1") (pinfunction "-1_A1") (pintype "passive"))
    )
    (net (code "134") (name "Net-(X201B--1)") (class "Default")
      (node (ref "R204") (pin "1") (pinfunction "1_1") (pintype "passive"))
      (node (ref "X201") (pin "A2") (pinfunction "-1_A2") (pintype "passive"))
    )
    (net (code "135") (name "Net-(X201D--1)") (class "Default")
      (node (ref "R203") (pin "1") (pinfunction "1_1") (pintype "passive"))
      (node (ref "X201") (pin "A4") (pinfunction "-1_A4") (pintype "passive"))
    )
    (net (code "136") (name "Net-(X201F--1)") (class "Default")
      (node (ref "R202") (pin "1") (pinfunction "1_1") (pintype "passive"))
      (node (ref "X201") (pin "A6") (pinfunction "-1_A6") (pintype "passive"))
    )
    (net (code "137") (name "Net-(X201H--1)") (class "Default")
      (node (ref "R201") (pin "1") (pinfunction "1_1") (pintype "passive"))
      (node (ref "X201") (pin "A8") (pinfunction "-1_A8") (pintype "passive"))
    )
    (net (code "138") (name "Net-(X202B--1)") (class "Default")
      (node (ref "R208") (pin "1") (pinfunction "1_1") (pintype "passive"))
      (node (ref "X202") (pin "A2") (pinfunction "-1_A2") (pintype "passive"))
    )
    (net (code "139") (name "Net-(X202D--1)") (class "Default")
      (node (ref "R207") (pin "1") (pinfunction "1_1") (pintype "passive"))
      (node (ref "X202") (pin "A4") (pinfunction "-1_A4") (pintype "passive"))
    )
    (net (code "140") (name "Net-(X202F--1)") (class "Default")
      (node (ref "R206") (pin "1") (pinfunction "1_1") (pintype "passive"))
      (node (ref "X202") (pin "A6") (pinfunction "-1_A6") (pintype "passive"))
    )
    (net (code "141") (name "Net-(X202H--1)") (class "Default")
      (node (ref "R205") (pin "1") (pinfunction "1_1") (pintype "passive"))
      (node (ref "X202") (pin "A8") (pinfunction "-1_A8") (pintype "passive"))
    )
    (net (code "142") (name "Net-(X203B--1)") (class "Default")
      (node (ref "R212") (pin "1") (pinfunction "1_1") (pintype "passive"))
      (node (ref "X203") (pin "A2") (pinfunction "-1_A2") (pintype "passive"))
    )
    (net (code "143") (name "Net-(X203D--1)") (class "Default")
      (node (ref "R211") (pin "1") (pinfunction "1_1") (pintype "passive"))
      (node (ref "X203") (pin "A4") (pinfunction "-1_A4") (pintype "passive"))
    )
    (net (code "144") (name "Net-(X203F--1)") (class "Default")
      (node (ref "R210") (pin "1") (pinfunction "1_1") (pintype "passive"))
      (node (ref "X203") (pin "A6") (pinfunction "-1_A6") (pintype "passive"))
    )
    (net (code "145") (name "Net-(X203H--1)") (class "Default")
      (node (ref "R209") (pin "1") (pinfunction "1_1") (pintype "passive"))
      (node (ref "X203") (pin "A8") (pinfunction "-1_A8") (pintype "passive"))
    )
    (net (code "146") (name "Net-(X204B--1)") (class "Default")
      (node (ref "R216") (pin "1") (pinfunction "1_1") (pintype "passive"))
      (node (ref "X204") (pin "A2") (pinfunction "-1_A2") (pintype "passive"))
    )
    (net (code "147") (name "Net-(X204D--1)") (class "Default")
      (node (ref "R215") (pin "1") (pinfunction "1_1") (pintype "passive"))
      (node (ref "X204") (pin "A4") (pinfunction "-1_A4") (pintype "passive"))
    )
    (net (code "148") (name "Net-(X204F--1)") (class "Default")
      (node (ref "R214") (pin "1") (pinfunction "1_1") (pintype "passive"))
      (node (ref "X204") (pin "A6") (pinfunction "-1_A6") (pintype "passive"))
    )
    (net (code "149") (name "Net-(X204H--1)") (class "Default")
      (node (ref "R213") (pin "1") (pinfunction "1_1") (pintype "passive"))
      (node (ref "X204") (pin "A8") (pinfunction "-1_A8") (pintype "passive"))
    )
    (net (code "150") (name "OUT0") (class "Default")
      (node (ref "IC104") (pin "15") (pinfunction "QA_15") (pintype "output"))
      (node (ref "R301") (pin "1") (pinfunction "1_1") (pintype "passive"))
    )
    (net (code "151") (name "OUT1") (class "Default")
      (node (ref "IC104") (pin "1") (pinfunction "QB_1") (pintype "output"))
      (node (ref "R302") (pin "1") (pinfunction "1_1") (pintype "passive"))
    )
    (net (code "152") (name "OUT2") (class "Default")
      (node (ref "IC104") (pin "2") (pinfunction "QC_2") (pintype "output"))
      (node (ref "R303") (pin "1") (pinfunction "1_1") (pintype "passive"))
    )
    (net (code "153") (name "OUT3") (class "Default")
      (node (ref "IC104") (pin "3") (pinfunction "QD_3") (pintype "output"))
      (node (ref "R304") (pin "1") (pinfunction "1_1") (pintype "passive"))
    )
    (net (code "154") (name "OUT4") (class "Default")
      (node (ref "IC104") (pin "4") (pinfunction "QE_4") (pintype "output"))
      (node (ref "R305") (pin "1") (pinfunction "1_1") (pintype "passive"))
    )
    (net (code "155") (name "OUT5") (class "Default")
      (node (ref "IC104") (pin "5") (pinfunction "QF_5") (pintype "output"))
      (node (ref "R306") (pin "1") (pinfunction "1_1") (pintype "passive"))
    )
    (net (code "156") (name "OUT6") (class "Default")
      (node (ref "IC104") (pin "6") (pinfunction "QG_6") (pintype "output"))
      (node (ref "R307") (pin "1") (pinfunction "1_1") (pintype "passive"))
    )
    (net (code "157") (name "OUT7") (class "Default")
      (node (ref "IC104") (pin "7") (pinfunction "QH_7") (pintype "output"))
      (node (ref "R308") (pin "1") (pinfunction "1_1") (pintype "passive"))
    )
    (net (code "158") (name "OUT8") (class "Default")
      (node (ref "IC105") (pin "15") (pinfunction "QA_15") (pintype "output"))
      (node (ref "R309") (pin "1") (pinfunction "1_1") (pintype "passive"))
    )
    (net (code "159") (name "OUT9") (class "Default")
      (node (ref "IC105") (pin "1") (pinfunction "QB_1") (pintype "output"))
      (node (ref "R310") (pin "1") (pinfunction "1_1") (pintype "passive"))
    )
    (net (code "160") (name "OUT10") (class "Default")
      (node (ref "IC105") (pin "2") (pinfunction "QC_2") (pintype "output"))
      (node (ref "R311") (pin "1") (pinfunction "1_1") (pintype "passive"))
    )
    (net (code "161") (name "OUT11") (class "Default")
      (node (ref "IC105") (pin "3") (pinfunction "QD_3") (pintype "output"))
      (node (ref "R312") (pin "1") (pinfunction "1_1") (pintype "passive"))
    )
    (net (code "162") (name "OUT12") (class "Default")
      (node (ref "IC105") (pin "4") (pinfunction "QE_4") (pintype "output"))
      (node (ref "R313") (pin "1") (pinfunction "1_1") (pintype "passive"))
    )
    (net (code "163") (name "OUT13") (class "Default")
      (node (ref "IC105") (pin "5") (pinfunction "QF_5") (pintype "output"))
      (node (ref "R314") (pin "1") (pinfunction "1_1") (pintype "passive"))
    )
    (net (code "164") (name "OUT14") (class "Default")
      (node (ref "IC105") (pin "6") (pinfunction "QG_6") (pintype "output"))
      (node (ref "R315") (pin "1") (pinfunction "1_1") (pintype "passive"))
    )
    (net (code "165") (name "OUT15") (class "Default")
      (node (ref "IC105") (pin "7") (pinfunction "QH_7") (pintype "output"))
      (node (ref "R316") (pin "1") (pinfunction "1_1") (pintype "passive"))
    )
    (net (code "166") (name "SCL") (class "Default")
      (node (ref "IC101") (pin "1") (pinfunction "(T0/XCK)PB0_1") (pintype "bidirectional"))
      (node (ref "IC102") (pin "6") (pinfunction "SCL_6") (pintype "bidirectional"))
    )
    (net (code "167") (name "SDA") (class "Default")
      (node (ref "IC101") (pin "2") (pinfunction "(T1)PB1_2") (pintype "bidirectional"))
      (node (ref "IC102") (pin "5") (pinfunction "SDA_5") (pintype "bidirectional"))
    )
    (net (code "168") (name "unconnected-(IC101-(AIN0{slash}INT2)PB2-Pad3)") (class "Default")
      (node (ref "IC101") (pin "3") (pinfunction "(AIN0/INT2)PB2_3") (pintype "bidirectional"))
    )
    (net (code "169") (name "unconnected-(IC101-(AIN1{slash}OC0)PB3-Pad4)") (class "Default")
      (node (ref "IC101") (pin "4") (pinfunction "(AIN1/OC0)PB3_4") (pintype "bidirectional"))
    )
    (net (code "170") (name "unconnected-(IC101-AREF-Pad32)") (class "Default")
      (node (ref "IC101") (pin "32") (pinfunction "AREF_32") (pintype "passive"))
    )
    (net (code "171") (name "unconnected-(IC101-XTAL1-Pad13)") (class "Default")
      (node (ref "IC101") (pin "13") (pinfunction "XTAL1_13") (pintype "bidirectional"))
    )
    (net (code "172") (name "unconnected-(IC101-XTAL2-Pad12)") (class "Default")
      (node (ref "IC101") (pin "12") (pinfunction "XTAL2_12") (pintype "bidirectional"))
    )
    (net (code "173") (name "unconnected-(IC102A-SQW{slash}~{INTB}-Pad7)") (class "Default")
      (node (ref "IC102") (pin "7") (pinfunction "SQW/~{INTB}_7") (pintype "open_collector"))
    )
    (net (code "174") (name "unconnected-(IC102A-~{INTA}-Pad3)") (class "Default")
      (node (ref "IC102") (pin "3") (pinfunction "~{INTA}_3") (pintype "open_collector"))
    )
    (net (code "175") (name "unconnected-(IC105A-QH*-Pad9)") (class "Default")
      (node (ref "IC105") (pin "9") (pinfunction "QH*_9") (pintype "output"))
    )
    (net (code "176") (name "unconnected-(X101A-B-1-PadB1)") (class "Default")
      (node (ref "X101") (pin "B1") (pinfunction "B-1_B1") (pintype "passive"))
    )
    (net (code "177") (name "unconnected-(X101B-B-1-PadB2)") (class "Default")
      (node (ref "X101") (pin "B2") (pinfunction "B-1_B2") (pintype "passive"))
    )
    (net (code "178") (name "unconnected-(X101C-B-1-PadB3)") (class "Default")
      (node (ref "X101") (pin "B3") (pinfunction "B-1_B3") (pintype "passive"))
    )
    (net (code "179") (name "unconnected-(X101D-B-1-PadB4)") (class "Default")
      (node (ref "X101") (pin "B4") (pinfunction "B-1_B4") (pintype "passive"))
    )
    (net (code "180") (name "unconnected-(X201A-B-1-PadB1)") (class "Default")
      (node (ref "X201") (pin "B1") (pinfunction "B-1_B1") (pintype "passive"))
    )
    (net (code "181") (name "unconnected-(X201B-B-1-PadB2)") (class "Default")
      (node (ref "X201") (pin "B2") (pinfunction "B-1_B2") (pintype "passive"))
    )
    (net (code "182") (name "unconnected-(X201C-B-1-PadB3)") (class "Default")
      (node (ref "X201") (pin "B3") (pinfunction "B-1_B3") (pintype "passive"))
    )
    (net (code "183") (name "unconnected-(X201D-B-1-PadB4)") (class "Default")
      (node (ref "X201") (pin "B4") (pinfunction "B-1_B4") (pintype "passive"))
    )
    (net (code "184") (name "unconnected-(X201E-B-1-PadB5)") (class "Default")
      (node (ref "X201") (pin "B5") (pinfunction "B-1_B5") (pintype "passive"))
    )
    (net (code "185") (name "unconnected-(X201F-B-1-PadB6)") (class "Default")
      (node (ref "X201") (pin "B6") (pinfunction "B-1_B6") (pintype "passive"))
    )
    (net (code "186") (name "unconnected-(X201G-B-1-PadB7)") (class "Default")
      (node (ref "X201") (pin "B7") (pinfunction "B-1_B7") (pintype "passive"))
    )
    (net (code "187") (name "unconnected-(X201H-B-1-PadB8)") (class "Default")
      (node (ref "X201") (pin "B8") (pinfunction "B-1_B8") (pintype "passive"))
    )
    (net (code "188") (name "unconnected-(X202A-B-1-PadB1)") (class "Default")
      (node (ref "X202") (pin "B1") (pinfunction "B-1_B1") (pintype "passive"))
    )
    (net (code "189") (name "unconnected-(X202B-B-1-PadB2)") (class "Default")
      (node (ref "X202") (pin "B2") (pinfunction "B-1_B2") (pintype "passive"))
    )
    (net (code "190") (name "unconnected-(X202C-B-1-PadB3)") (class "Default")
      (node (ref "X202") (pin "B3") (pinfunction "B-1_B3") (pintype "passive"))
    )
    (net (code "191") (name "unconnected-(X202D-B-1-PadB4)") (class "Default")
      (node (ref "X202") (pin "B4") (pinfunction "B-1_B4") (pintype "passive"))
    )
    (net (code "192") (name "unconnected-(X202E-B-1-PadB5)") (class "Default")
      (node (ref "X202") (pin "B5") (pinfunction "B-1_B5") (pintype "passive"))
    )
    (net (code "193") (name "unconnected-(X202F-B-1-PadB6)") (class "Default")
      (node (ref "X202") (pin "B6") (pinfunction "B-1_B6") (pintype "passive"))
    )
    (net (code "194") (name "unconnected-(X202G-B-1-PadB7)") (class "Default")
      (node (ref "X202") (pin "B7") (pinfunction "B-1_B7") (pintype "passive"))
    )
    (net (code "195") (name "unconnected-(X202H-B-1-PadB8)") (class "Default")
      (node (ref "X202") (pin "B8") (pinfunction "B-1_B8") (pintype "passive"))
    )
    (net (code "196") (name "unconnected-(X203A-B-1-PadB1)") (class "Default")
      (node (ref "X203") (pin "B1") (pinfunction "B-1_B1") (pintype "passive"))
    )
    (net (code "197") (name "unconnected-(X203B-B-1-PadB2)") (class "Default")
      (node (ref "X203") (pin "B2") (pinfunction "B-1_B2") (pintype "passive"))
    )
    (net (code "198") (name "unconnected-(X203C-B-1-PadB3)") (class "Default")
      (node (ref "X203") (pin "B3") (pinfunction "B-1_B3") (pintype "passive"))
    )
    (net (code "199") (name "unconnected-(X203D-B-1-PadB4)") (class "Default")
      (node (ref "X203") (pin "B4") (pinfunction "B-1_B4") (pintype "passive"))
    )
    (net (code "200") (name "unconnected-(X203E-B-1-PadB5)") (class "Default")
      (node (ref "X203") (pin "B5") (pinfunction "B-1_B5") (pintype "passive"))
    )
    (net (code "201") (name "unconnected-(X203F-B-1-PadB6)") (class "Default")
      (node (ref "X203") (pin "B6") (pinfunction "B-1_B6") (pintype "passive"))
    )
    (net (code "202") (name "unconnected-(X203G-B-1-PadB7)") (class "Default")
      (node (ref "X203") (pin "B7") (pinfunction "B-1_B7") (pintype "passive"))
    )
    (net (code "203") (name "unconnected-(X203H-B-1-PadB8)") (class "Default")
      (node (ref "X203") (pin "B8") (pinfunction "B-1_B8") (pintype "passive"))
    )
    (net (code "204") (name "unconnected-(X204A-B-1-PadB1)") (class "Default")
      (node (ref "X204") (pin "B1") (pinfunction "B-1_B1") (pintype "passive"))
    )
    (net (code "205") (name "unconnected-(X204B-B-1-PadB2)") (class "Default")
      (node (ref "X204") (pin "B2") (pinfunction "B-1_B2") (pintype "passive"))
    )
    (net (code "206") (name "unconnected-(X204C-B-1-PadB3)") (class "Default")
      (node (ref "X204") (pin "B3") (pinfunction "B-1_B3") (pintype "passive"))
    )
    (net (code "207") (name "unconnected-(X204D-B-1-PadB4)") (class "Default")
      (node (ref "X204") (pin "B4") (pinfunction "B-1_B4") (pintype "passive"))
    )
    (net (code "208") (name "unconnected-(X204E-B-1-PadB5)") (class "Default")
      (node (ref "X204") (pin "B5") (pinfunction "B-1_B5") (pintype "passive"))
    )
    (net (code "209") (name "unconnected-(X204F-B-1-PadB6)") (class "Default")
      (node (ref "X204") (pin "B6") (pinfunction "B-1_B6") (pintype "passive"))
    )
    (net (code "210") (name "unconnected-(X204G-B-1-PadB7)") (class "Default")
      (node (ref "X204") (pin "B7") (pinfunction "B-1_B7") (pintype "passive"))
    )
    (net (code "211") (name "unconnected-(X204H-B-1-PadB8)") (class "Default")
      (node (ref "X204") (pin "B8") (pinfunction "B-1_B8") (pintype "passive"))
    )
    (net (code "212") (name "unconnected-(X301A-B-1-PadB1)") (class "Default")
      (node (ref "X301") (pin "B1") (pinfunction "B-1_B1") (pintype "passive"))
    )
    (net (code "213") (name "unconnected-(X301B-B-1-PadB2)") (class "Default")
      (node (ref "X301") (pin "B2") (pinfunction "B-1_B2") (pintype "passive"))
    )
    (net (code "214") (name "unconnected-(X301C-B-1-PadB3)") (class "Default")
      (node (ref "X301") (pin "B3") (pinfunction "B-1_B3") (pintype "passive"))
    )
    (net (code "215") (name "unconnected-(X301D-B-1-PadB4)") (class "Default")
      (node (ref "X301") (pin "B4") (pinfunction "B-1_B4") (pintype "passive"))
    )
    (net (code "216") (name "unconnected-(X301E-B-1-PadB5)") (class "Default")
      (node (ref "X301") (pin "B5") (pinfunction "B-1_B5") (pintype "passive"))
    )
    (net (code "217") (name "unconnected-(X301F-B-1-PadB6)") (class "Default")
      (node (ref "X301") (pin "B6") (pinfunction "B-1_B6") (pintype "passive"))
    )
    (net (code "218") (name "unconnected-(X301G-B-1-PadB7)") (class "Default")
      (node (ref "X301") (pin "B7") (pinfunction "B-1_B7") (pintype "passive"))
    )
    (net (code "219") (name "unconnected-(X301H-B-1-PadB8)") (class "Default")
      (node (ref "X301") (pin "B8") (pinfunction "B-1_B8") (pintype "passive"))
    )
    (net (code "220") (name "unconnected-(X302A-B-1-PadB1)") (class "Default")
      (node (ref "X302") (pin "B1") (pinfunction "B-1_B1") (pintype "passive"))
    )
    (net (code "221") (name "unconnected-(X302B-B-1-PadB2)") (class "Default")
      (node (ref "X302") (pin "B2") (pinfunction "B-1_B2") (pintype "passive"))
    )
    (net (code "222") (name "unconnected-(X302C-B-1-PadB3)") (class "Default")
      (node (ref "X302") (pin "B3") (pinfunction "B-1_B3") (pintype "passive"))
    )
    (net (code "223") (name "unconnected-(X302D-B-1-PadB4)") (class "Default")
      (node (ref "X302") (pin "B4") (pinfunction "B-1_B4") (pintype "passive"))
    )
    (net (code "224") (name "unconnected-(X302E-B-1-PadB5)") (class "Default")
      (node (ref "X302") (pin "B5") (pinfunction "B-1_B5") (pintype "passive"))
    )
    (net (code "225") (name "unconnected-(X302F-B-1-PadB6)") (class "Default")
      (node (ref "X302") (pin "B6") (pinfunction "B-1_B6") (pintype "passive"))
    )
    (net (code "226") (name "unconnected-(X302G-B-1-PadB7)") (class "Default")
      (node (ref "X302") (pin "B7") (pinfunction "B-1_B7") (pintype "passive"))
    )
    (net (code "227") (name "unconnected-(X302H-B-1-PadB8)") (class "Default")
      (node (ref "X302") (pin "B8") (pinfunction "B-1_B8") (pintype "passive"))
    )
    (net (code "228") (name "unconnected-(X303A-B-1-PadB1)") (class "Default")
      (node (ref "X303") (pin "B1") (pinfunction "B-1_B1") (pintype "passive"))
    )
    (net (code "229") (name "unconnected-(X303B-B-1-PadB2)") (class "Default")
      (node (ref "X303") (pin "B2") (pinfunction "B-1_B2") (pintype "passive"))
    )
    (net (code "230") (name "unconnected-(X303C-B-1-PadB3)") (class "Default")
      (node (ref "X303") (pin "B3") (pinfunction "B-1_B3") (pintype "passive"))
    )
    (net (code "231") (name "unconnected-(X303D-B-1-PadB4)") (class "Default")
      (node (ref "X303") (pin "B4") (pinfunction "B-1_B4") (pintype "passive"))
    )
    (net (code "232") (name "unconnected-(X303E-B-1-PadB5)") (class "Default")
      (node (ref "X303") (pin "B5") (pinfunction "B-1_B5") (pintype "passive"))
    )
    (net (code "233") (name "unconnected-(X303F-B-1-PadB6)") (class "Default")
      (node (ref "X303") (pin "B6") (pinfunction "B-1_B6") (pintype "passive"))
    )
    (net (code "234") (name "unconnected-(X303G-B-1-PadB7)") (class "Default")
      (node (ref "X303") (pin "B7") (pinfunction "B-1_B7") (pintype "passive"))
    )
    (net (code "235") (name "unconnected-(X303H-B-1-PadB8)") (class "Default")
      (node (ref "X303") (pin "B8") (pinfunction "B-1_B8") (pintype "passive"))
    )
    (net (code "236") (name "unconnected-(X304A-B-1-PadB1)") (class "Default")
      (node (ref "X304") (pin "B1") (pinfunction "B-1_B1") (pintype "passive"))
    )
    (net (code "237") (name "unconnected-(X304B-B-1-PadB2)") (class "Default")
      (node (ref "X304") (pin "B2") (pinfunction "B-1_B2") (pintype "passive"))
    )
    (net (code "238") (name "unconnected-(X304C-B-1-PadB3)") (class "Default")
      (node (ref "X304") (pin "B3") (pinfunction "B-1_B3") (pintype "passive"))
    )
    (net (code "239") (name "unconnected-(X304D-B-1-PadB4)") (class "Default")
      (node (ref "X304") (pin "B4") (pinfunction "B-1_B4") (pintype "passive"))
    )
    (net (code "240") (name "unconnected-(X304E-B-1-PadB5)") (class "Default")
      (node (ref "X304") (pin "B5") (pinfunction "B-1_B5") (pintype "passive"))
    )
    (net (code "241") (name "unconnected-(X304F-B-1-PadB6)") (class "Default")
      (node (ref "X304") (pin "B6") (pinfunction "B-1_B6") (pintype "passive"))
    )
    (net (code "242") (name "unconnected-(X304G-B-1-PadB7)") (class "Default")
      (node (ref "X304") (pin "B7") (pinfunction "B-1_B7") (pintype "passive"))
    )
    (net (code "243") (name "unconnected-(X304H-B-1-PadB8)") (class "Default")
      (node (ref "X304") (pin "B8") (pinfunction "B-1_B8") (pintype "passive"))
    )
    (net (code "244") (name "~{R}") (class "Default")
      (node (ref "IC101") (pin "21") (pinfunction "(OC2)PD7_21") (pintype "bidirectional"))
      (node (ref "IC104") (pin "10") (pinfunction "SCL_10") (pintype "input"))
      (node (ref "IC104") (pin "13") (pinfunction "RCL_13") (pintype "input"))
      (node (ref "IC105") (pin "10") (pinfunction "SCL_10") (pintype "input"))
      (node (ref "IC105") (pin "13") (pinfunction "RCL_13") (pintype "input"))
    )
  )
)
